# SmartIMU_Sch.net
KiCad netlist of a schematic drawn in Altium Designer
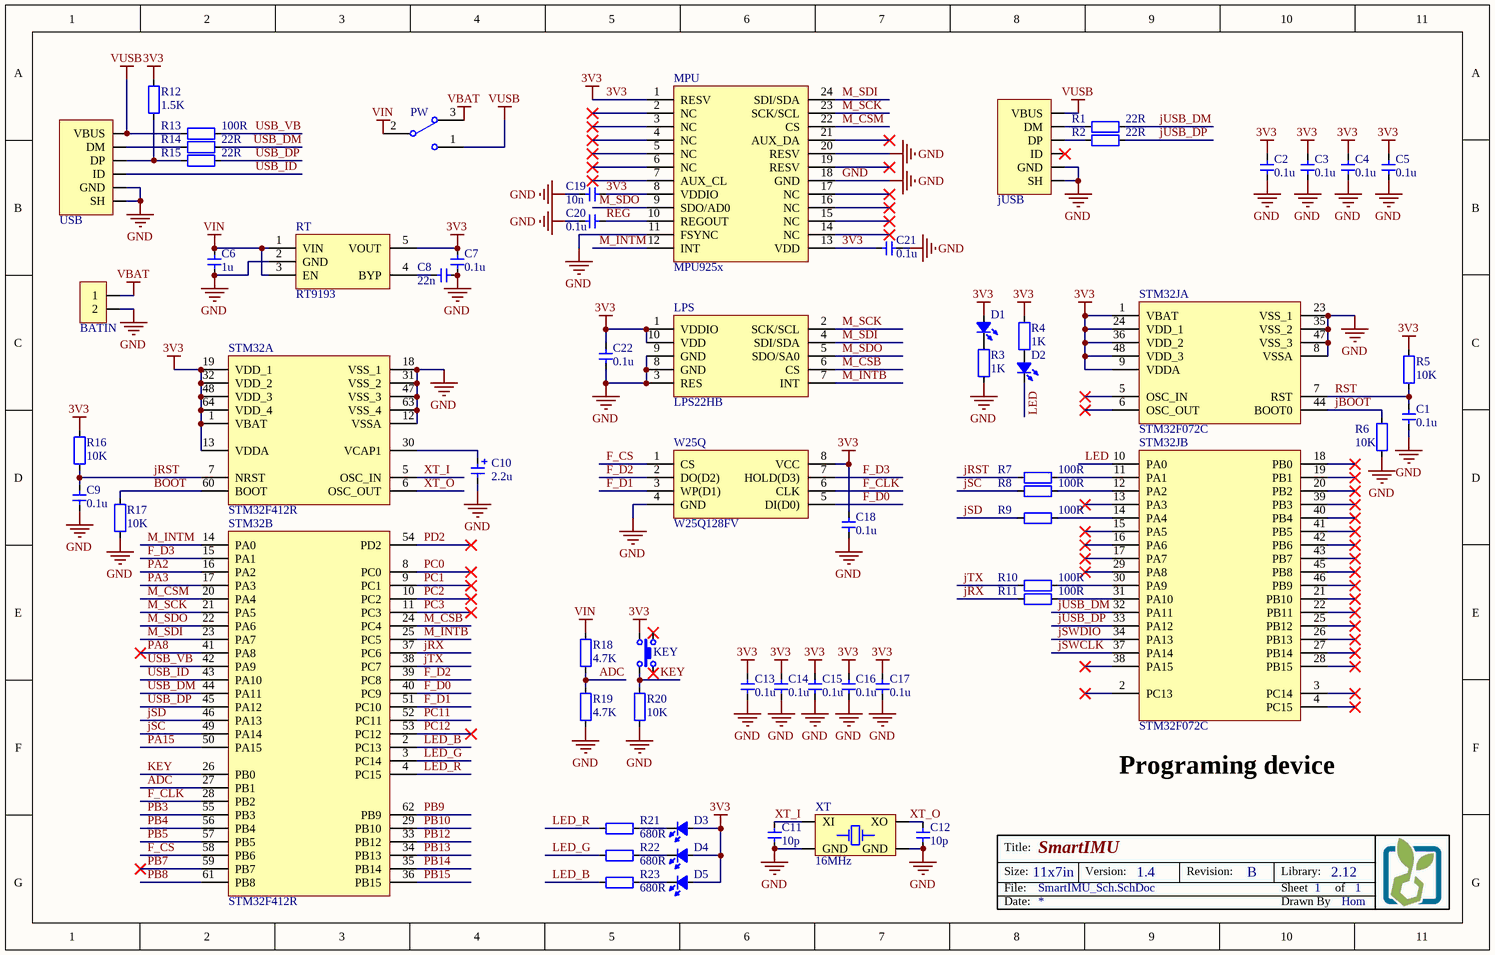
[diagram p0: SmartIMU_Sch.SchDoc]

(export (version "E")
  (design (tool "Eeschema 10.0.6"))
  (components
    (comp (ref "BATIN")
      (value "MX1.25_2P")
      (footprint "PCB_Connector:MX1.25_S90_2P")
      (description "MX")
      (libsource (lib "SCH_Connector") (part "MX1.25_2P"))
    )
    (comp (ref "C1")
      (value "0.1u")
      (footprint "PCB_PassiveCap:CAP_0603")
      (description "Capacitor")
      (fields (field (name "Comment") "Cap_0603"))
      (libsource (lib "SCH_Passive") (part "Cap_0603"))
    )
    (comp (ref "C2")
      (value "0.1u")
      (footprint "PCB_PassiveCap:CAP_0603")
      (description "Capacitor")
      (fields (field (name "Comment") "Cap_0603"))
      (libsource (lib "SCH_Passive") (part "Cap_0603"))
    )
    (comp (ref "C3")
      (value "0.1u")
      (footprint "PCB_PassiveCap:CAP_0603")
      (description "Capacitor")
      (fields (field (name "Comment") "Cap_0603"))
      (libsource (lib "SCH_Passive") (part "Cap_0603"))
    )
    (comp (ref "C4")
      (value "0.1u")
      (footprint "PCB_PassiveCap:CAP_0603")
      (description "Capacitor")
      (fields (field (name "Comment") "Cap_0603"))
      (libsource (lib "SCH_Passive") (part "Cap_0603"))
    )
    (comp (ref "C5")
      (value "0.1u")
      (footprint "PCB_PassiveCap:CAP_0603")
      (description "Capacitor")
      (fields (field (name "Comment") "Cap_0603"))
      (libsource (lib "SCH_Passive") (part "Cap_0603"))
    )
    (comp (ref "C6")
      (value "1u")
      (footprint "PCB_PassiveCap:CAP_0603")
      (description "Capacitor")
      (fields (field (name "Comment") "Cap_0603"))
      (libsource (lib "SCH_Passive") (part "Cap_0603"))
    )
    (comp (ref "C7")
      (value "0.1u")
      (footprint "PCB_PassiveCap:CAP_0603")
      (description "Capacitor")
      (fields (field (name "Comment") "Cap_0603"))
      (libsource (lib "SCH_Passive") (part "Cap_0603"))
    )
    (comp (ref "C8")
      (value "22n")
      (footprint "PCB_PassiveCap:CAP_0603")
      (description "Capacitor")
      (fields (field (name "Comment") "Cap_0603"))
      (libsource (lib "SCH_Passive") (part "Cap_0603"))
    )
    (comp (ref "C9")
      (value "0.1u")
      (footprint "PCB_PassiveCap:CAP_0603")
      (description "Capacitor")
      (fields (field (name "Comment") "Cap_0603"))
      (libsource (lib "SCH_Passive") (part "Cap_0603"))
    )
    (comp (ref "C10")
      (value "2.2u")
      (footprint "PCB_PassiveCap:CAP_TAN_P0805")
      (description "Capacitor")
      (fields (field (name "Comment") "Cap_Tan_0805"))
      (libsource (lib "SCH_Passive") (part "Cap_Tan_0805"))
    )
    (comp (ref "C11")
      (value "10p")
      (footprint "PCB_PassiveCap:CAP_0603")
      (description "Capacitor")
      (fields (field (name "Comment") "Cap_0603"))
      (libsource (lib "SCH_Passive") (part "Cap_0603"))
    )
    (comp (ref "C12")
      (value "10p")
      (footprint "PCB_PassiveCap:CAP_0603")
      (description "Capacitor")
      (fields (field (name "Comment") "Cap_0603"))
      (libsource (lib "SCH_Passive") (part "Cap_0603"))
    )
    (comp (ref "C13")
      (value "0.1u")
      (footprint "PCB_PassiveCap:CAP_0603")
      (description "Capacitor")
      (fields (field (name "Comment") "Cap_0603"))
      (libsource (lib "SCH_Passive") (part "Cap_0603"))
    )
    (comp (ref "C14")
      (value "0.1u")
      (footprint "PCB_PassiveCap:CAP_0603")
      (description "Capacitor")
      (fields (field (name "Comment") "Cap_0603"))
      (libsource (lib "SCH_Passive") (part "Cap_0603"))
    )
    (comp (ref "C15")
      (value "0.1u")
      (footprint "PCB_PassiveCap:CAP_0603")
      (description "Capacitor")
      (fields (field (name "Comment") "Cap_0603"))
      (libsource (lib "SCH_Passive") (part "Cap_0603"))
    )
    (comp (ref "C16")
      (value "0.1u")
      (footprint "PCB_PassiveCap:CAP_0603")
      (description "Capacitor")
      (fields (field (name "Comment") "Cap_0603"))
      (libsource (lib "SCH_Passive") (part "Cap_0603"))
    )
    (comp (ref "C17")
      (value "0.1u")
      (footprint "PCB_PassiveCap:CAP_0603")
      (description "Capacitor")
      (fields (field (name "Comment") "Cap_0603"))
      (libsource (lib "SCH_Passive") (part "Cap_0603"))
    )
    (comp (ref "C18")
      (value "0.1u")
      (footprint "PCB_PassiveCap:CAP_0603")
      (description "Capacitor")
      (fields (field (name "Comment") "Cap_0603"))
      (libsource (lib "SCH_Passive") (part "Cap_0603"))
    )
    (comp (ref "C19")
      (value "10n")
      (footprint "PCB_PassiveCap:CAP_0603")
      (description "Capacitor")
      (fields (field (name "Comment") "Cap_0603"))
      (libsource (lib "SCH_Passive") (part "Cap_0603"))
    )
    (comp (ref "C20")
      (value "0.1u")
      (footprint "PCB_PassiveCap:CAP_0603")
      (description "Capacitor")
      (fields (field (name "Comment") "Cap_0603"))
      (libsource (lib "SCH_Passive") (part "Cap_0603"))
    )
    (comp (ref "C21")
      (value "0.1u")
      (footprint "PCB_PassiveCap:CAP_0603")
      (description "Capacitor")
      (fields (field (name "Comment") "Cap_0603"))
      (libsource (lib "SCH_Passive") (part "Cap_0603"))
    )
    (comp (ref "C22")
      (value "0.1u")
      (footprint "PCB_PassiveCap:CAP_0603")
      (description "Capacitor")
      (fields (field (name "Comment") "Cap_0603"))
      (libsource (lib "SCH_Passive") (part "Cap_0603"))
    )
    (comp (ref "D1")
      (value "LED_0603")
      (footprint "PCB_ActiveLED:LED_0603_YELLOW")
      (description "LED")
      (libsource (lib "SCH_Active") (part "LED_0603"))
    )
    (comp (ref "D2")
      (value "LED_0603")
      (footprint "PCB_ActiveLED:LED_0603_ORANGE")
      (description "LED")
      (libsource (lib "SCH_Active") (part "LED_0603"))
    )
    (comp (ref "D3")
      (value "LED_0603")
      (footprint "PCB_ActiveLED:LED_0603_RED")
      (description "LED")
      (libsource (lib "SCH_Active") (part "LED_0603"))
    )
    (comp (ref "D4")
      (value "LED_0603")
      (footprint "PCB_ActiveLED:LED_0603_GREEN")
      (description "LED")
      (libsource (lib "SCH_Active") (part "LED_0603"))
    )
    (comp (ref "D5")
      (value "LED_0603")
      (footprint "PCB_ActiveLED:LED_0603_BLUE")
      (description "LED")
      (libsource (lib "SCH_Active") (part "LED_0603"))
    )
    (comp (ref "jUSB")
      (value "USB_Micro")
      (footprint "PCB_USB:USB_Micro-AB")
      (description "USB")
      (libsource (lib "SCH_USB") (part "USB_Micro"))
    )
    (comp (ref "KEY")
      (value "ButtonTACT")
      (footprint "PCB_Switch:ButtonTACT_3.5*3.55_90")
      (description "Button")
      (libsource (lib "SCH_Switch") (part "ButtonTACT"))
    )
    (comp (ref "LPS")
      (value "LPS22HB")
      (footprint "PCB_IntegratedCircuit:HCLGA-2x2_10")
      (description "Sensor Pressure")
      (libsource (lib "SCH_IntegratedCircuit") (part "LPS22HB"))
    )
    (comp (ref "MPU")
      (value "MPU925x")
      (footprint "PCB_IntegratedCircuit:QFN_P0.4_24")
      (description "Sensor Motion")
      (libsource (lib "SCH_IntegratedCircuit") (part "MPU925x"))
    )
    (comp (ref "PW")
      (value "SwitchSPDT_2.8x6.6_90")
      (footprint "PCB_Switch:SwitchSPDT_2.8X6.6_90")
      (description "Switch")
      (libsource (lib "SCH_Switch") (part "SwitchSPDT_2.8x6.6_90"))
    )
    (comp (ref "R1")
      (value "22R")
      (footprint "PCB_PassiveRes:RES_0603")
      (description "Resistor")
      (fields (field (name "Comment") "Res_0603"))
      (libsource (lib "") (part "Res_0603_2"))
    )
    (comp (ref "R2")
      (value "22R")
      (footprint "PCB_PassiveRes:RES_0603")
      (description "Resistor")
      (fields (field (name "Comment") "Res_0603"))
      (libsource (lib "") (part "Res_0603_2"))
    )
    (comp (ref "R3")
      (value "1K")
      (footprint "PCB_PassiveRes:RES_0603")
      (description "Resistor")
      (fields (field (name "Comment") "Res_0603"))
      (libsource (lib "SCH_Passive") (part "Res_0603"))
    )
    (comp (ref "R4")
      (value "1K")
      (footprint "PCB_PassiveRes:RES_0603")
      (description "Resistor")
      (fields (field (name "Comment") "Res_0603"))
      (libsource (lib "SCH_Passive") (part "Res_0603"))
    )
    (comp (ref "R5")
      (value "10K")
      (footprint "PCB_PassiveRes:RES_0603")
      (description "Resistor")
      (fields (field (name "Comment") "Res_0603"))
      (libsource (lib "SCH_Passive") (part "Res_0603"))
    )
    (comp (ref "R6")
      (value "10K")
      (footprint "PCB_PassiveRes:RES_0603")
      (description "Resistor")
      (fields (field (name "Comment") "Res_0603"))
      (libsource (lib "SCH_Passive") (part "Res_0603"))
    )
    (comp (ref "R7")
      (value "100R")
      (footprint "PCB_PassiveRes:RES_0603")
      (description "Resistor")
      (fields (field (name "Comment") "Res_0603"))
      (libsource (lib "") (part "Res_0603_2"))
    )
    (comp (ref "R8")
      (value "100R")
      (footprint "PCB_PassiveRes:RES_0603")
      (description "Resistor")
      (fields (field (name "Comment") "Res_0603"))
      (libsource (lib "") (part "Res_0603_2"))
    )
    (comp (ref "R9")
      (value "100R")
      (footprint "PCB_PassiveRes:RES_0603")
      (description "Resistor")
      (fields (field (name "Comment") "Res_0603"))
      (libsource (lib "") (part "Res_0603_2"))
    )
    (comp (ref "R10")
      (value "100R")
      (footprint "PCB_PassiveRes:RES_0603")
      (description "Resistor")
      (fields (field (name "Comment") "Res_0603"))
      (libsource (lib "") (part "Res_0603_2"))
    )
    (comp (ref "R11")
      (value "100R")
      (footprint "PCB_PassiveRes:RES_0603")
      (description "Resistor")
      (fields (field (name "Comment") "Res_0603"))
      (libsource (lib "") (part "Res_0603_2"))
    )
    (comp (ref "R12")
      (value "1.5K")
      (footprint "PCB_PassiveRes:RES_0603")
      (description "Resistor")
      (fields (field (name "Comment") "Res_0603"))
      (libsource (lib "") (part "Res_0603_3"))
    )
    (comp (ref "R13")
      (value "100R")
      (footprint "PCB_PassiveRes:RES_0603")
      (description "Resistor")
      (fields (field (name "Comment") "Res_0603"))
      (libsource (lib "") (part "Res_0603_1"))
    )
    (comp (ref "R14")
      (value "22R")
      (footprint "PCB_PassiveRes:RES_0603")
      (description "Resistor")
      (fields (field (name "Comment") "Res_0603"))
      (libsource (lib "") (part "Res_0603_1"))
    )
    (comp (ref "R15")
      (value "22R")
      (footprint "PCB_PassiveRes:RES_0603")
      (description "Resistor")
      (fields (field (name "Comment") "Res_0603"))
      (libsource (lib "") (part "Res_0603_1"))
    )
    (comp (ref "R16")
      (value "10K")
      (footprint "PCB_PassiveRes:RES_0603")
      (description "Resistor")
      (fields (field (name "Comment") "Res_0603"))
      (libsource (lib "SCH_Passive") (part "Res_0603"))
    )
    (comp (ref "R17")
      (value "10K")
      (footprint "PCB_PassiveRes:RES_0603")
      (description "Resistor")
      (fields (field (name "Comment") "Res_0603"))
      (libsource (lib "SCH_Passive") (part "Res_0603"))
    )
    (comp (ref "R18")
      (value "4.7K")
      (footprint "PCB_PassiveRes:RES_0603")
      (description "Resistor")
      (fields (field (name "Comment") "Res_0603"))
      (libsource (lib "") (part "Res_0603_3"))
    )
    (comp (ref "R19")
      (value "4.7K")
      (footprint "PCB_PassiveRes:RES_0603")
      (description "Resistor")
      (fields (field (name "Comment") "Res_0603"))
      (libsource (lib "") (part "Res_0603_3"))
    )
    (comp (ref "R20")
      (value "10K")
      (footprint "PCB_PassiveRes:RES_0603")
      (description "Resistor")
      (fields (field (name "Comment") "Res_0603"))
      (libsource (lib "SCH_Passive") (part "Res_0603"))
    )
    (comp (ref "R21")
      (value "680R")
      (footprint "PCB_PassiveRes:RES_0603")
      (description "Resistor")
      (fields (field (name "Comment") "Res_0603"))
      (libsource (lib "") (part "Res_0603_1"))
    )
    (comp (ref "R22")
      (value "680R")
      (footprint "PCB_PassiveRes:RES_0603")
      (description "Resistor")
      (fields (field (name "Comment") "Res_0603"))
      (libsource (lib "") (part "Res_0603_1"))
    )
    (comp (ref "R23")
      (value "680R")
      (footprint "PCB_PassiveRes:RES_0603")
      (description "Resistor")
      (fields (field (name "Comment") "Res_0603"))
      (libsource (lib "") (part "Res_0603_1"))
    )
    (comp (ref "RT")
      (value "RT9193")
      (footprint "PCB_IntegratedCircuit:SOT23-5")
      (description "Power")
      (libsource (lib "SCH_IntegratedCircuit") (part "RT9193"))
    )
    (comp (ref "STM32")
      (value "STM32F412R")
      (footprint "PCB_IntegratedCircuit:LQFP_P0.5_64")
      (description "MCU")
      (libsource (lib "SCH_IntegratedCircuit") (part "STM32F412R/446R"))
    )
    (comp (ref "STM32J")
      (value "STM32F072C")
      (footprint "PCB_IntegratedCircuit:LQFP_P0.5_48")
      (description "MCU")
      (libsource (lib "SCH_IntegratedCircuit") (part "STM32F103C"))
    )
    (comp (ref "USB")
      (value "USB_Micro")
      (footprint "PCB_USB:USB_Micro-AB")
      (description "USB")
      (libsource (lib "SCH_USB") (part "USB_Micro"))
    )
    (comp (ref "W25Q")
      (value "W25Q128FV")
      (footprint "PCB_IntegratedCircuit:SON_P1.27H_8")
      (description "FLASH")
      (libsource (lib "SCH_IntegratedCircuit") (part "W25Q_8"))
    )
    (comp (ref "XT")
      (value "16MHz")
      (footprint "PCB_Oscillator:XT_2520_4")
      (description "Crystal Oscillator")
      (fields (field (name "Comment") "XTAL_2520_4P"))
      (libsource (lib "SCH_Oscillator") (part "XTAL_2520_4P"))
    )
  )
  (nets
    (net (code "1") (name "/ADC") (class "Default")
      (node (ref "R18") (pin "2") (pinfunction "2_2") (pintype "passive"))
      (node (ref "R19") (pin "1") (pinfunction "1_1") (pintype "passive"))
      (node (ref "STM32") (pin "27") (pinfunction "PB1_27") (pintype "passive"))
    )
    (net (code "2") (name "/BOOT") (class "Default")
      (node (ref "R17") (pin "2") (pinfunction "2_2") (pintype "passive"))
      (node (ref "STM32") (pin "60") (pinfunction "BOOT_60") (pintype "passive"))
    )
    (net (code "3") (name "/F_CLK") (class "Default")
      (node (ref "STM32") (pin "28") (pinfunction "PB2_28") (pintype "passive"))
      (node (ref "W25Q") (pin "6") (pinfunction "CLK_6") (pintype "passive"))
    )
    (net (code "4") (name "/F_CS") (class "Default")
      (node (ref "STM32") (pin "58") (pinfunction "PB6_58") (pintype "passive"))
      (node (ref "W25Q") (pin "1") (pinfunction "CS_1") (pintype "passive"))
    )
    (net (code "5") (name "/F_D0") (class "Default")
      (node (ref "STM32") (pin "40") (pinfunction "PC9_40") (pintype "passive"))
      (node (ref "W25Q") (pin "5") (pinfunction "DI(D0)_5") (pintype "passive"))
    )
    (net (code "6") (name "/F_D1") (class "Default")
      (node (ref "STM32") (pin "51") (pinfunction "PC10_51") (pintype "passive"))
      (node (ref "W25Q") (pin "3") (pinfunction "WP(D1)_3") (pintype "passive"))
    )
    (net (code "7") (name "/F_D2") (class "Default")
      (node (ref "STM32") (pin "39") (pinfunction "PC8_39") (pintype "passive"))
      (node (ref "W25Q") (pin "2") (pinfunction "DO(D2)_2") (pintype "passive"))
    )
    (net (code "8") (name "/F_D3") (class "Default")
      (node (ref "STM32") (pin "15") (pinfunction "PA1_15") (pintype "passive"))
      (node (ref "W25Q") (pin "7") (pinfunction "HOLD(D3)_7") (pintype "passive"))
    )
    (net (code "9") (name "/KEY") (class "Default")
      (node (ref "KEY") (pin "4") (pinfunction "4_4") (pintype "passive"))
      (node (ref "R20") (pin "2") (pinfunction "2_2") (pintype "passive"))
      (node (ref "STM32") (pin "26") (pinfunction "PB0_26") (pintype "passive"))
    )
    (net (code "10") (name "/LED") (class "Default")
      (node (ref "D2") (pin "2") (pinfunction "K_2") (pintype "passive"))
      (node (ref "STM32J") (pin "10") (pinfunction "PA0_10") (pintype "passive"))
    )
    (net (code "11") (name "/LED_B") (class "Default")
      (node (ref "R23") (pin "2") (pinfunction "2_2") (pintype "passive"))
      (node (ref "STM32") (pin "2") (pinfunction "PC13_2") (pintype "passive"))
    )
    (net (code "12") (name "/LED_G") (class "Default")
      (node (ref "R22") (pin "2") (pinfunction "2_2") (pintype "passive"))
      (node (ref "STM32") (pin "3") (pinfunction "PC14_3") (pintype "passive"))
    )
    (net (code "13") (name "/LED_R") (class "Default")
      (node (ref "R21") (pin "2") (pinfunction "2_2") (pintype "passive"))
      (node (ref "STM32") (pin "4") (pinfunction "PC15_4") (pintype "passive"))
    )
    (net (code "14") (name "/M_CSB") (class "Default")
      (node (ref "LPS") (pin "6") (pinfunction "CS_6") (pintype "passive"))
      (node (ref "STM32") (pin "24") (pinfunction "PC4_24") (pintype "passive"))
    )
    (net (code "15") (name "/M_CSM") (class "Default")
      (node (ref "MPU") (pin "22") (pinfunction "CS_22") (pintype "passive"))
      (node (ref "STM32") (pin "20") (pinfunction "PA4_20") (pintype "passive"))
    )
    (net (code "16") (name "/M_INTB") (class "Default")
      (node (ref "LPS") (pin "7") (pinfunction "INT_7") (pintype "passive"))
      (node (ref "STM32") (pin "25") (pinfunction "PC5_25") (pintype "passive"))
    )
    (net (code "17") (name "/M_INTM") (class "Default")
      (node (ref "MPU") (pin "12") (pinfunction "INT_12") (pintype "passive"))
      (node (ref "STM32") (pin "14") (pinfunction "PA0_14") (pintype "passive"))
    )
    (net (code "18") (name "/M_SCK") (class "Default")
      (node (ref "LPS") (pin "2") (pinfunction "SCK/SCL_2") (pintype "passive"))
      (node (ref "MPU") (pin "23") (pinfunction "SCK/SCL_23") (pintype "passive"))
      (node (ref "STM32") (pin "21") (pinfunction "PA5_21") (pintype "passive"))
    )
    (net (code "19") (name "/M_SDI") (class "Default")
      (node (ref "LPS") (pin "4") (pinfunction "SDI/SDA_4") (pintype "passive"))
      (node (ref "MPU") (pin "24") (pinfunction "SDI/SDA_24") (pintype "passive"))
      (node (ref "STM32") (pin "23") (pinfunction "PA7_23") (pintype "passive"))
    )
    (net (code "20") (name "/M_SDO") (class "Default")
      (node (ref "LPS") (pin "5") (pinfunction "SDO/SA0_5") (pintype "passive"))
      (node (ref "MPU") (pin "9") (pinfunction "SDO/AD0_9") (pintype "passive"))
      (node (ref "STM32") (pin "22") (pinfunction "PA6_22") (pintype "passive"))
    )
    (net (code "21") (name "/PA2") (class "Default")
      (node (ref "STM32") (pin "16") (pinfunction "PA2_16") (pintype "passive"))
    )
    (net (code "22") (name "/PA3") (class "Default")
      (node (ref "STM32") (pin "17") (pinfunction "PA3_17") (pintype "passive"))
    )
    (net (code "23") (name "/PA8") (class "Default")
      (node (ref "STM32") (pin "41") (pinfunction "PA8_41") (pintype "passive+no_connect"))
    )
    (net (code "24") (name "/PA15") (class "Default")
      (node (ref "STM32") (pin "50") (pinfunction "PA15_50") (pintype "passive"))
    )
    (net (code "25") (name "/PB3") (class "Default")
      (node (ref "STM32") (pin "55") (pinfunction "PB3_55") (pintype "passive"))
    )
    (net (code "26") (name "/PB4") (class "Default")
      (node (ref "STM32") (pin "56") (pinfunction "PB4_56") (pintype "passive"))
    )
    (net (code "27") (name "/PB5") (class "Default")
      (node (ref "STM32") (pin "57") (pinfunction "PB5_57") (pintype "passive"))
    )
    (net (code "28") (name "/PB7") (class "Default")
      (node (ref "STM32") (pin "59") (pinfunction "PB7_59") (pintype "passive+no_connect"))
    )
    (net (code "29") (name "/PB8") (class "Default")
      (node (ref "STM32") (pin "61") (pinfunction "PB8_61") (pintype "passive"))
    )
    (net (code "30") (name "/PB9") (class "Default")
      (node (ref "STM32") (pin "62") (pinfunction "PB9_62") (pintype "passive"))
    )
    (net (code "31") (name "/PB10") (class "Default")
      (node (ref "STM32") (pin "29") (pinfunction "PB10_29") (pintype "passive"))
    )
    (net (code "32") (name "/PB12") (class "Default")
      (node (ref "STM32") (pin "33") (pinfunction "PB12_33") (pintype "passive"))
    )
    (net (code "33") (name "/PB13") (class "Default")
      (node (ref "STM32") (pin "34") (pinfunction "PB13_34") (pintype "passive"))
    )
    (net (code "34") (name "/PB14") (class "Default")
      (node (ref "STM32") (pin "35") (pinfunction "PB14_35") (pintype "passive"))
    )
    (net (code "35") (name "/PB15") (class "Default")
      (node (ref "STM32") (pin "36") (pinfunction "PB15_36") (pintype "passive"))
    )
    (net (code "36") (name "/PC0") (class "Default")
      (node (ref "STM32") (pin "8") (pinfunction "PC0_8") (pintype "passive+no_connect"))
    )
    (net (code "37") (name "/PC1") (class "Default")
      (node (ref "STM32") (pin "9") (pinfunction "PC1_9") (pintype "passive+no_connect"))
    )
    (net (code "38") (name "/PC2") (class "Default")
      (node (ref "STM32") (pin "10") (pinfunction "PC2_10") (pintype "passive+no_connect"))
    )
    (net (code "39") (name "/PC3") (class "Default")
      (node (ref "STM32") (pin "11") (pinfunction "PC3_11") (pintype "passive+no_connect"))
    )
    (net (code "40") (name "/PC11") (class "Default")
      (node (ref "STM32") (pin "52") (pinfunction "PC11_52") (pintype "passive"))
    )
    (net (code "41") (name "/PC12") (class "Default")
      (node (ref "STM32") (pin "53") (pinfunction "PC12_53") (pintype "passive+no_connect"))
    )
    (net (code "42") (name "/PD2") (class "Default")
      (node (ref "STM32") (pin "54") (pinfunction "PD2_54") (pintype "passive+no_connect"))
    )
    (net (code "43") (name "/REG") (class "Default")
      (node (ref "C20") (pin "2") (pinfunction "2_2") (pintype "passive"))
      (node (ref "MPU") (pin "10") (pinfunction "REGOUT_10") (pintype "passive"))
    )
    (net (code "44") (name "/RST") (class "Default")
      (node (ref "C1") (pin "2") (pinfunction "2_2") (pintype "passive"))
      (node (ref "R5") (pin "1") (pinfunction "1_1") (pintype "passive"))
      (node (ref "STM32J") (pin "7") (pinfunction "RST_7") (pintype "passive"))
    )
    (net (code "45") (name "/USB_DM") (class "Default")
      (node (ref "R14") (pin "1") (pinfunction "1_1") (pintype "passive"))
      (node (ref "STM32") (pin "44") (pinfunction "PA11_44") (pintype "passive"))
    )
    (net (code "46") (name "/USB_DP") (class "Default")
      (node (ref "R15") (pin "1") (pinfunction "1_1") (pintype "passive"))
      (node (ref "STM32") (pin "45") (pinfunction "PA12_45") (pintype "passive"))
    )
    (net (code "47") (name "/USB_ID") (class "Default")
      (node (ref "STM32") (pin "43") (pinfunction "PA10_43") (pintype "passive"))
      (node (ref "USB") (pin "4") (pinfunction "ID_4") (pintype "passive"))
    )
    (net (code "48") (name "/USB_VB") (class "Default")
      (node (ref "R13") (pin "1") (pinfunction "1_1") (pintype "passive"))
      (node (ref "STM32") (pin "42") (pinfunction "PA9_42") (pintype "passive"))
    )
    (net (code "49") (name "/XT_I") (class "Default")
      (node (ref "C11") (pin "1") (pinfunction "1_1") (pintype "passive"))
      (node (ref "STM32") (pin "5") (pinfunction "OSC_IN_5") (pintype "passive"))
      (node (ref "XT") (pin "1") (pinfunction "XI_1") (pintype "passive"))
    )
    (net (code "50") (name "/XT_O") (class "Default")
      (node (ref "C12") (pin "1") (pinfunction "1_1") (pintype "passive"))
      (node (ref "STM32") (pin "6") (pinfunction "OSC_OUT_6") (pintype "passive"))
      (node (ref "XT") (pin "3") (pinfunction "XO_3") (pintype "passive"))
    )
    (net (code "51") (name "/jBOOT") (class "Default")
      (node (ref "R6") (pin "2") (pinfunction "2_2") (pintype "passive"))
      (node (ref "STM32J") (pin "44") (pinfunction "BOOT0_44") (pintype "passive"))
    )
    (net (code "52") (name "/jRST") (class "Default")
      (node (ref "C9") (pin "2") (pinfunction "2_2") (pintype "passive"))
      (node (ref "R16") (pin "1") (pinfunction "1_1") (pintype "passive"))
      (node (ref "R7") (pin "1") (pinfunction "1_1") (pintype "passive"))
      (node (ref "STM32") (pin "7") (pinfunction "NRST_7") (pintype "passive"))
    )
    (net (code "53") (name "/jRX") (class "Default")
      (node (ref "R11") (pin "1") (pinfunction "1_1") (pintype "passive"))
      (node (ref "STM32") (pin "37") (pinfunction "PC6_37") (pintype "passive"))
    )
    (net (code "54") (name "/jSC") (class "Default")
      (node (ref "R8") (pin "1") (pinfunction "1_1") (pintype "passive"))
      (node (ref "STM32") (pin "49") (pinfunction "PA14_49") (pintype "passive"))
    )
    (net (code "55") (name "/jSD") (class "Default")
      (node (ref "R9") (pin "1") (pinfunction "1_1") (pintype "passive"))
      (node (ref "STM32") (pin "46") (pinfunction "PA13_46") (pintype "passive"))
    )
    (net (code "56") (name "/jSWCLK") (class "Default")
      (node (ref "STM32J") (pin "37") (pinfunction "PA14_37") (pintype "passive"))
    )
    (net (code "57") (name "/jSWDIO") (class "Default")
      (node (ref "STM32J") (pin "34") (pinfunction "PA13_34") (pintype "passive"))
    )
    (net (code "58") (name "/jTX") (class "Default")
      (node (ref "R10") (pin "1") (pinfunction "1_1") (pintype "passive"))
      (node (ref "STM32") (pin "38") (pinfunction "PC7_38") (pintype "passive"))
    )
    (net (code "59") (name "/jUSB_DM") (class "Default")
      (node (ref "R1") (pin "2") (pinfunction "2_2") (pintype "passive"))
      (node (ref "STM32J") (pin "32") (pinfunction "PA11_32") (pintype "passive"))
    )
    (net (code "60") (name "/jUSB_DP") (class "Default")
      (node (ref "R2") (pin "2") (pinfunction "2_2") (pintype "passive"))
      (node (ref "STM32J") (pin "33") (pinfunction "PA12_33") (pintype "passive"))
    )
    (net (code "61") (name "3V3") (class "Default")
      (node (ref "C13") (pin "1") (pinfunction "1_1") (pintype "passive"))
      (node (ref "C14") (pin "1") (pinfunction "1_1") (pintype "passive"))
      (node (ref "C15") (pin "1") (pinfunction "1_1") (pintype "passive"))
      (node (ref "C16") (pin "1") (pinfunction "1_1") (pintype "passive"))
      (node (ref "C17") (pin "2") (pinfunction "2_2") (pintype "passive"))
      (node (ref "C18") (pin "1") (pinfunction "1_1") (pintype "passive"))
      (node (ref "C19") (pin "2") (pinfunction "2_2") (pintype "passive"))
      (node (ref "C2") (pin "2") (pinfunction "2_2") (pintype "passive"))
      (node (ref "C21") (pin "2") (pinfunction "2_2") (pintype "passive"))
      (node (ref "C22") (pin "1") (pinfunction "1_1") (pintype "passive"))
      (node (ref "C3") (pin "2") (pinfunction "2_2") (pintype "passive"))
      (node (ref "C4") (pin "2") (pinfunction "2_2") (pintype "passive"))
      (node (ref "C5") (pin "2") (pinfunction "2_2") (pintype "passive"))
      (node (ref "C7") (pin "2") (pinfunction "2_2") (pintype "passive"))
      (node (ref "D1") (pin "1") (pinfunction "A_1") (pintype "passive"))
      (node (ref "D3") (pin "1") (pinfunction "A_1") (pintype "passive"))
      (node (ref "D4") (pin "1") (pinfunction "A_1") (pintype "passive"))
      (node (ref "D5") (pin "1") (pinfunction "A_1") (pintype "passive"))
      (node (ref "KEY") (pin "3") (pinfunction "3_3") (pintype "passive"))
      (node (ref "LPS") (pin "1") (pinfunction "VDDIO_1") (pintype "passive"))
      (node (ref "LPS") (pin "10") (pinfunction "VDD_10") (pintype "passive"))
      (node (ref "MPU") (pin "1") (pinfunction "RESV_1") (pintype "passive"))
      (node (ref "MPU") (pin "13") (pinfunction "VDD_13") (pintype "passive"))
      (node (ref "MPU") (pin "8") (pinfunction "VDDIO_8") (pintype "passive"))
      (node (ref "R12") (pin "1") (pinfunction "1_1") (pintype "passive"))
      (node (ref "R16") (pin "2") (pinfunction "2_2") (pintype "passive"))
      (node (ref "R4") (pin "2") (pinfunction "2_2") (pintype "passive"))
      (node (ref "R5") (pin "2") (pinfunction "2_2") (pintype "passive"))
      (node (ref "RT") (pin "5") (pinfunction "VOUT_5") (pintype "passive"))
      (node (ref "STM32") (pin "1") (pinfunction "VBAT_1") (pintype "passive"))
      (node (ref "STM32") (pin "13") (pinfunction "VDDA_13") (pintype "passive"))
      (node (ref "STM32") (pin "19") (pinfunction "VDD_1_19") (pintype "passive"))
      (node (ref "STM32") (pin "32") (pinfunction "VDD_2_32") (pintype "passive"))
      (node (ref "STM32") (pin "48") (pinfunction "VDD_3_48") (pintype "passive"))
      (node (ref "STM32") (pin "64") (pinfunction "VDD_4_64") (pintype "passive"))
      (node (ref "STM32J") (pin "1") (pinfunction "VBAT_1") (pintype "passive"))
      (node (ref "STM32J") (pin "24") (pinfunction "VDD_1_24") (pintype "passive"))
      (node (ref "STM32J") (pin "36") (pinfunction "VDD_2_36") (pintype "passive"))
      (node (ref "STM32J") (pin "48") (pinfunction "VDD_3_48") (pintype "passive"))
      (node (ref "STM32J") (pin "9") (pinfunction "VDDA_9") (pintype "passive"))
      (node (ref "W25Q") (pin "8") (pinfunction "VCC_8") (pintype "passive"))
    )
    (net (code "62") (name "GND") (class "Default")
      (node (ref "BATIN") (pin "2") (pinfunction "2_2") (pintype "passive"))
      (node (ref "C1") (pin "1") (pinfunction "1_1") (pintype "passive"))
      (node (ref "C10") (pin "2") (pinfunction "2_2") (pintype "passive"))
      (node (ref "C11") (pin "2") (pinfunction "2_2") (pintype "passive"))
      (node (ref "C12") (pin "2") (pinfunction "2_2") (pintype "passive"))
      (node (ref "C13") (pin "2") (pinfunction "2_2") (pintype "passive"))
      (node (ref "C14") (pin "2") (pinfunction "2_2") (pintype "passive"))
      (node (ref "C15") (pin "2") (pinfunction "2_2") (pintype "passive"))
      (node (ref "C16") (pin "2") (pinfunction "2_2") (pintype "passive"))
      (node (ref "C17") (pin "1") (pinfunction "1_1") (pintype "passive"))
      (node (ref "C18") (pin "2") (pinfunction "2_2") (pintype "passive"))
      (node (ref "C19") (pin "1") (pinfunction "1_1") (pintype "passive"))
      (node (ref "C2") (pin "1") (pinfunction "1_1") (pintype "passive"))
      (node (ref "C20") (pin "1") (pinfunction "1_1") (pintype "passive"))
      (node (ref "C21") (pin "1") (pinfunction "1_1") (pintype "passive"))
      (node (ref "C22") (pin "2") (pinfunction "2_2") (pintype "passive"))
      (node (ref "C3") (pin "1") (pinfunction "1_1") (pintype "passive"))
      (node (ref "C4") (pin "1") (pinfunction "1_1") (pintype "passive"))
      (node (ref "C5") (pin "1") (pinfunction "1_1") (pintype "passive"))
      (node (ref "C6") (pin "1") (pinfunction "1_1") (pintype "passive"))
      (node (ref "C7") (pin "1") (pinfunction "1_1") (pintype "passive"))
      (node (ref "C8") (pin "1") (pinfunction "1_1") (pintype "passive"))
      (node (ref "C9") (pin "1") (pinfunction "1_1") (pintype "passive"))
      (node (ref "LPS") (pin "3") (pinfunction "RES_3") (pintype "passive"))
      (node (ref "LPS") (pin "8") (pinfunction "GND_8") (pintype "passive"))
      (node (ref "LPS") (pin "9") (pinfunction "GND_9") (pintype "passive"))
      (node (ref "MPU") (pin "11") (pinfunction "FSYNC_11") (pintype "passive"))
      (node (ref "MPU") (pin "18") (pinfunction "GND_18") (pintype "passive"))
      (node (ref "MPU") (pin "20") (pinfunction "RESV_20") (pintype "passive"))
      (node (ref "R17") (pin "1") (pinfunction "1_1") (pintype "passive"))
      (node (ref "R19") (pin "2") (pinfunction "2_2") (pintype "passive"))
      (node (ref "R20") (pin "1") (pinfunction "1_1") (pintype "passive"))
      (node (ref "R3") (pin "1") (pinfunction "1_1") (pintype "passive"))
      (node (ref "R6") (pin "1") (pinfunction "1_1") (pintype "passive"))
      (node (ref "RT") (pin "2") (pinfunction "GND_2") (pintype "passive"))
      (node (ref "STM32") (pin "12") (pinfunction "VSSA_12") (pintype "passive"))
      (node (ref "STM32") (pin "18") (pinfunction "VSS_1_18") (pintype "passive"))
      (node (ref "STM32") (pin "31") (pinfunction "VSS_2_31") (pintype "passive"))
      (node (ref "STM32") (pin "47") (pinfunction "VSS_3_47") (pintype "passive"))
      (node (ref "STM32") (pin "63") (pinfunction "VSS_4_63") (pintype "passive"))
      (node (ref "STM32J") (pin "23") (pinfunction "VSS_1_23") (pintype "passive"))
      (node (ref "STM32J") (pin "35") (pinfunction "VSS_2_35") (pintype "passive"))
      (node (ref "STM32J") (pin "47") (pinfunction "VSS_3_47") (pintype "passive"))
      (node (ref "STM32J") (pin "8") (pinfunction "VSSA_8") (pintype "passive"))
      (node (ref "USB") (pin "0") (pinfunction "SH_0") (pintype "passive"))
      (node (ref "USB") (pin "5") (pinfunction "GND_5") (pintype "passive"))
      (node (ref "W25Q") (pin "4") (pinfunction "GND_4") (pintype "passive"))
      (node (ref "XT") (pin "2") (pinfunction "GND_2") (pintype "passive"))
      (node (ref "XT") (pin "4") (pinfunction "GND_4") (pintype "passive"))
      (node (ref "jUSB") (pin "0") (pinfunction "SH_0") (pintype "passive"))
      (node (ref "jUSB") (pin "5") (pinfunction "GND_5") (pintype "passive"))
    )
    (net (code "63") (name "Net-(D1-K)") (class "Default")
      (node (ref "D1") (pin "2") (pinfunction "K_2") (pintype "passive"))
      (node (ref "R3") (pin "2") (pinfunction "2_2") (pintype "passive"))
    )
    (net (code "64") (name "Net-(D2-A)") (class "Default")
      (node (ref "D2") (pin "1") (pinfunction "A_1") (pintype "passive"))
      (node (ref "R4") (pin "1") (pinfunction "1_1") (pintype "passive"))
    )
    (net (code "65") (name "Net-(D3-K)") (class "Default")
      (node (ref "D3") (pin "2") (pinfunction "K_2") (pintype "passive"))
      (node (ref "R21") (pin "1") (pinfunction "1_1") (pintype "passive"))
    )
    (net (code "66") (name "Net-(D4-K)") (class "Default")
      (node (ref "D4") (pin "2") (pinfunction "K_2") (pintype "passive"))
      (node (ref "R22") (pin "1") (pinfunction "1_1") (pintype "passive"))
    )
    (net (code "67") (name "Net-(D5-K)") (class "Default")
      (node (ref "D5") (pin "2") (pinfunction "K_2") (pintype "passive"))
      (node (ref "R23") (pin "1") (pinfunction "1_1") (pintype "passive"))
    )
    (net (code "68") (name "Net-(RT-BYP)") (class "Default")
      (node (ref "C8") (pin "2") (pinfunction "2_2") (pintype "passive"))
      (node (ref "RT") (pin "4") (pinfunction "BYP_4") (pintype "passive"))
    )
    (net (code "69") (name "Net-(STM32A-VCAP1)") (class "Default")
      (node (ref "C10") (pin "1") (pinfunction "1_1") (pintype "passive"))
      (node (ref "STM32") (pin "30") (pinfunction "VCAP1_30") (pintype "passive"))
    )
    (net (code "70") (name "Net-(STM32JB-PA1)") (class "Default")
      (node (ref "R7") (pin "2") (pinfunction "2_2") (pintype "passive"))
      (node (ref "STM32J") (pin "11") (pinfunction "PA1_11") (pintype "passive"))
    )
    (net (code "71") (name "Net-(STM32JB-PA2)") (class "Default")
      (node (ref "R8") (pin "2") (pinfunction "2_2") (pintype "passive"))
      (node (ref "STM32J") (pin "12") (pinfunction "PA2_12") (pintype "passive"))
    )
    (net (code "72") (name "Net-(STM32JB-PA4)") (class "Default")
      (node (ref "R9") (pin "2") (pinfunction "2_2") (pintype "passive"))
      (node (ref "STM32J") (pin "14") (pinfunction "PA4_14") (pintype "passive"))
    )
    (net (code "73") (name "Net-(STM32JB-PA9)") (class "Default")
      (node (ref "R10") (pin "2") (pinfunction "2_2") (pintype "passive"))
      (node (ref "STM32J") (pin "30") (pinfunction "PA9_30") (pintype "passive"))
    )
    (net (code "74") (name "Net-(STM32JB-PA10)") (class "Default")
      (node (ref "R11") (pin "2") (pinfunction "2_2") (pintype "passive"))
      (node (ref "STM32J") (pin "31") (pinfunction "PA10_31") (pintype "passive"))
    )
    (net (code "75") (name "Net-(USB-DM)") (class "Default")
      (node (ref "R14") (pin "2") (pinfunction "2_2") (pintype "passive"))
      (node (ref "USB") (pin "2") (pinfunction "DM_2") (pintype "passive"))
    )
    (net (code "76") (name "Net-(USB-DP)") (class "Default")
      (node (ref "R12") (pin "2") (pinfunction "2_2") (pintype "passive"))
      (node (ref "R15") (pin "2") (pinfunction "2_2") (pintype "passive"))
      (node (ref "USB") (pin "3") (pinfunction "DP_3") (pintype "passive"))
    )
    (net (code "77") (name "Net-(jUSB-DM)") (class "Default")
      (node (ref "R1") (pin "1") (pinfunction "1_1") (pintype "passive"))
      (node (ref "jUSB") (pin "2") (pinfunction "DM_2") (pintype "passive"))
    )
    (net (code "78") (name "Net-(jUSB-DP)") (class "Default")
      (node (ref "R2") (pin "1") (pinfunction "1_1") (pintype "passive"))
      (node (ref "jUSB") (pin "3") (pinfunction "DP_3") (pintype "passive"))
    )
    (net (code "79") (name "VBAT") (class "Default")
      (node (ref "BATIN") (pin "1") (pinfunction "1_1") (pintype "passive"))
      (node (ref "PW") (pin "3") (pinfunction "3_3") (pintype "passive"))
    )
    (net (code "80") (name "VIN") (class "Default")
      (node (ref "C6") (pin "2") (pinfunction "2_2") (pintype "passive"))
      (node (ref "PW") (pin "2") (pinfunction "2_2") (pintype "passive"))
      (node (ref "R18") (pin "1") (pinfunction "1_1") (pintype "passive"))
      (node (ref "RT") (pin "1") (pinfunction "VIN_1") (pintype "passive"))
      (node (ref "RT") (pin "3") (pinfunction "EN_3") (pintype "power_in"))
    )
    (net (code "81") (name "VUSB") (class "Default")
      (node (ref "PW") (pin "1") (pinfunction "1_1") (pintype "passive"))
      (node (ref "R13") (pin "2") (pinfunction "2_2") (pintype "passive"))
      (node (ref "USB") (pin "1") (pinfunction "VBUS_1") (pintype "passive"))
      (node (ref "jUSB") (pin "1") (pinfunction "VBUS_1") (pintype "passive"))
    )
    (net (code "82") (name "unconnected-(KEY-Pad1)") (class "Default")
      (node (ref "KEY") (pin "1") (pinfunction "1_1") (pintype "passive+no_connect"))
    )
    (net (code "83") (name "unconnected-(KEY-Pad2)") (class "Default")
      (node (ref "KEY") (pin "2") (pinfunction "2_2") (pintype "passive+no_connect"))
    )
    (net (code "84") (name "unconnected-(MPU-AUX_CL-Pad7)") (class "Default")
      (node (ref "MPU") (pin "7") (pinfunction "AUX_CL_7") (pintype "passive+no_connect"))
    )
    (net (code "85") (name "unconnected-(MPU-AUX_DA-Pad21)") (class "Default")
      (node (ref "MPU") (pin "21") (pinfunction "AUX_DA_21") (pintype "passive+no_connect"))
    )
    (net (code "86") (name "unconnected-(MPU-NC-Pad2)") (class "Default")
      (node (ref "MPU") (pin "2") (pinfunction "NC_2") (pintype "passive+no_connect"))
    )
    (net (code "87") (name "unconnected-(MPU-NC-Pad3)") (class "Default")
      (node (ref "MPU") (pin "3") (pinfunction "NC_3") (pintype "passive+no_connect"))
    )
    (net (code "88") (name "unconnected-(MPU-NC-Pad4)") (class "Default")
      (node (ref "MPU") (pin "4") (pinfunction "NC_4") (pintype "passive+no_connect"))
    )
    (net (code "89") (name "unconnected-(MPU-NC-Pad5)") (class "Default")
      (node (ref "MPU") (pin "5") (pinfunction "NC_5") (pintype "passive+no_connect"))
    )
    (net (code "90") (name "unconnected-(MPU-NC-Pad6)") (class "Default")
      (node (ref "MPU") (pin "6") (pinfunction "NC_6") (pintype "passive+no_connect"))
    )
    (net (code "91") (name "unconnected-(MPU-NC-Pad14)") (class "Default")
      (node (ref "MPU") (pin "14") (pinfunction "NC_14") (pintype "passive+no_connect"))
    )
    (net (code "92") (name "unconnected-(MPU-NC-Pad15)") (class "Default")
      (node (ref "MPU") (pin "15") (pinfunction "NC_15") (pintype "passive+no_connect"))
    )
    (net (code "93") (name "unconnected-(MPU-NC-Pad16)") (class "Default")
      (node (ref "MPU") (pin "16") (pinfunction "NC_16") (pintype "passive+no_connect"))
    )
    (net (code "94") (name "unconnected-(MPU-NC-Pad17)") (class "Default")
      (node (ref "MPU") (pin "17") (pinfunction "NC_17") (pintype "passive+no_connect"))
    )
    (net (code "95") (name "unconnected-(MPU-RESV-Pad19)") (class "Default")
      (node (ref "MPU") (pin "19") (pinfunction "RESV_19") (pintype "passive+no_connect"))
    )
    (net (code "96") (name "unconnected-(STM32JA-OSC_IN-Pad5)") (class "Default")
      (node (ref "STM32J") (pin "5") (pinfunction "OSC_IN_5") (pintype "passive+no_connect"))
    )
    (net (code "97") (name "unconnected-(STM32JA-OSC_OUT-Pad6)") (class "Default")
      (node (ref "STM32J") (pin "6") (pinfunction "OSC_OUT_6") (pintype "passive+no_connect"))
    )
    (net (code "98") (name "unconnected-(STM32JB-PA3-Pad13)") (class "Default")
      (node (ref "STM32J") (pin "13") (pinfunction "PA3_13") (pintype "passive+no_connect"))
    )
    (net (code "99") (name "unconnected-(STM32JB-PA5-Pad15)") (class "Default")
      (node (ref "STM32J") (pin "15") (pinfunction "PA5_15") (pintype "passive+no_connect"))
    )
    (net (code "100") (name "unconnected-(STM32JB-PA6-Pad16)") (class "Default")
      (node (ref "STM32J") (pin "16") (pinfunction "PA6_16") (pintype "passive+no_connect"))
    )
    (net (code "101") (name "unconnected-(STM32JB-PA7-Pad17)") (class "Default")
      (node (ref "STM32J") (pin "17") (pinfunction "PA7_17") (pintype "passive+no_connect"))
    )
    (net (code "102") (name "unconnected-(STM32JB-PA8-Pad29)") (class "Default")
      (node (ref "STM32J") (pin "29") (pinfunction "PA8_29") (pintype "passive+no_connect"))
    )
    (net (code "103") (name "unconnected-(STM32JB-PA15-Pad38)") (class "Default")
      (node (ref "STM32J") (pin "38") (pinfunction "PA15_38") (pintype "passive+no_connect"))
    )
    (net (code "104") (name "unconnected-(STM32JB-PB0-Pad18)") (class "Default")
      (node (ref "STM32J") (pin "18") (pinfunction "PB0_18") (pintype "passive+no_connect"))
    )
    (net (code "105") (name "unconnected-(STM32JB-PB1-Pad19)") (class "Default")
      (node (ref "STM32J") (pin "19") (pinfunction "PB1_19") (pintype "passive+no_connect"))
    )
    (net (code "106") (name "unconnected-(STM32JB-PB2-Pad20)") (class "Default")
      (node (ref "STM32J") (pin "20") (pinfunction "PB2_20") (pintype "passive+no_connect"))
    )
    (net (code "107") (name "unconnected-(STM32JB-PB3-Pad39)") (class "Default")
      (node (ref "STM32J") (pin "39") (pinfunction "PB3_39") (pintype "passive+no_connect"))
    )
    (net (code "108") (name "unconnected-(STM32JB-PB4-Pad40)") (class "Default")
      (node (ref "STM32J") (pin "40") (pinfunction "PB4_40") (pintype "passive+no_connect"))
    )
    (net (code "109") (name "unconnected-(STM32JB-PB5-Pad41)") (class "Default")
      (node (ref "STM32J") (pin "41") (pinfunction "PB5_41") (pintype "passive+no_connect"))
    )
    (net (code "110") (name "unconnected-(STM32JB-PB6-Pad42)") (class "Default")
      (node (ref "STM32J") (pin "42") (pinfunction "PB6_42") (pintype "passive+no_connect"))
    )
    (net (code "111") (name "unconnected-(STM32JB-PB7-Pad43)") (class "Default")
      (node (ref "STM32J") (pin "43") (pinfunction "PB7_43") (pintype "passive+no_connect"))
    )
    (net (code "112") (name "unconnected-(STM32JB-PB8-Pad45)") (class "Default")
      (node (ref "STM32J") (pin "45") (pinfunction "PB8_45") (pintype "passive+no_connect"))
    )
    (net (code "113") (name "unconnected-(STM32JB-PB9-Pad46)") (class "Default")
      (node (ref "STM32J") (pin "46") (pinfunction "PB9_46") (pintype "passive+no_connect"))
    )
    (net (code "114") (name "unconnected-(STM32JB-PB10-Pad21)") (class "Default")
      (node (ref "STM32J") (pin "21") (pinfunction "PB10_21") (pintype "passive+no_connect"))
    )
    (net (code "115") (name "unconnected-(STM32JB-PB11-Pad22)") (class "Default")
      (node (ref "STM32J") (pin "22") (pinfunction "PB11_22") (pintype "passive+no_connect"))
    )
    (net (code "116") (name "unconnected-(STM32JB-PB12-Pad25)") (class "Default")
      (node (ref "STM32J") (pin "25") (pinfunction "PB12_25") (pintype "passive+no_connect"))
    )
    (net (code "117") (name "unconnected-(STM32JB-PB13-Pad26)") (class "Default")
      (node (ref "STM32J") (pin "26") (pinfunction "PB13_26") (pintype "passive+no_connect"))
    )
    (net (code "118") (name "unconnected-(STM32JB-PB14-Pad27)") (class "Default")
      (node (ref "STM32J") (pin "27") (pinfunction "PB14_27") (pintype "passive+no_connect"))
    )
    (net (code "119") (name "unconnected-(STM32JB-PB15-Pad28)") (class "Default")
      (node (ref "STM32J") (pin "28") (pinfunction "PB15_28") (pintype "passive+no_connect"))
    )
    (net (code "120") (name "unconnected-(STM32JB-PC13-Pad2)") (class "Default")
      (node (ref "STM32J") (pin "2") (pinfunction "PC13_2") (pintype "passive+no_connect"))
    )
    (net (code "121") (name "unconnected-(STM32JB-PC14-Pad3)") (class "Default")
      (node (ref "STM32J") (pin "3") (pinfunction "PC14_3") (pintype "passive+no_connect"))
    )
    (net (code "122") (name "unconnected-(STM32JB-PC15-Pad4)") (class "Default")
      (node (ref "STM32J") (pin "4") (pinfunction "PC15_4") (pintype "passive+no_connect"))
    )
    (net (code "123") (name "unconnected-(jUSB-ID-Pad4)") (class "Default")
      (node (ref "jUSB") (pin "4") (pinfunction "ID_4") (pintype "passive+no_connect"))
    )
  )
)
